# bluetooth-v12.net
KiCad netlist of a schematic drawn in EAGLE
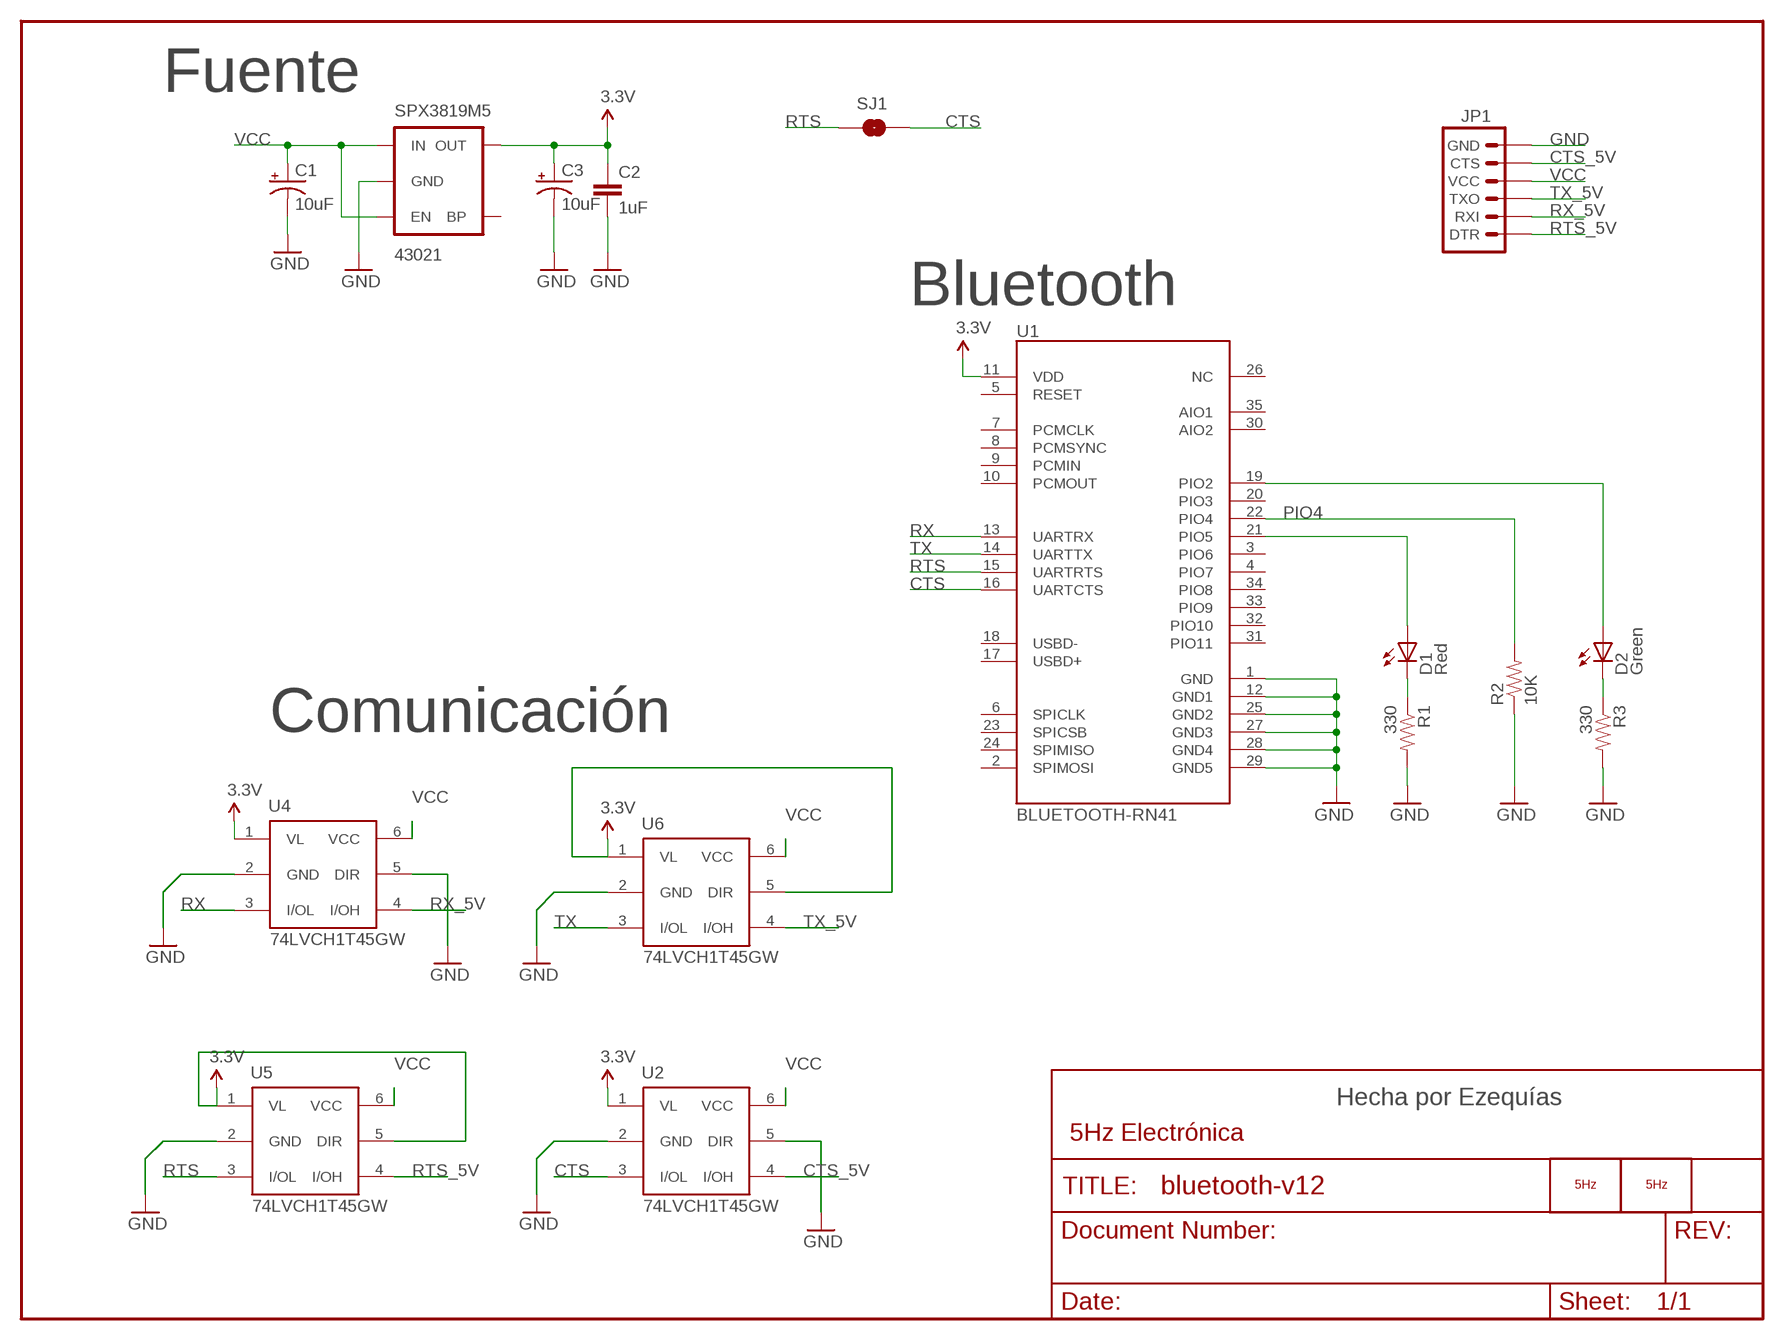
[diagram p0: schematic, sheet 1]

(export (version "E")
  (design (tool "Eeschema 10.0.6"))
  (components
    (comp (ref "C1")
      (value "10uF")
      (footprint "eagle-import:EIA3216")
      (libsource (lib "eagle-import") (part "CAP_POL1206"))
    )
    (comp (ref "C2")
      (value "1uF")
      (footprint "eagle-import:0603-CAP")
      (libsource (lib "eagle-import") (part "CAP0603-CAP"))
    )
    (comp (ref "C3")
      (value "10uF")
      (footprint "eagle-import:EIA3216")
      (libsource (lib "eagle-import") (part "CAP_POL1206"))
    )
    (comp (ref "D1")
      (value "Red")
      (footprint "eagle-import:LED-0603")
      (libsource (lib "eagle-import") (part "LED0603"))
    )
    (comp (ref "D2")
      (value "Green")
      (footprint "eagle-import:LED-0603")
      (libsource (lib "eagle-import") (part "LED0603"))
    )
    (comp (ref "JP1")
      (value "ARDUINO_SERIAL_PROGRAMPTH")
      (footprint "eagle-import:1X06")
      (libsource (lib "eagle-import") (part "ARDUINO_SERIAL_PROGRAMPTH"))
    )
    (comp (ref "LOGO2")
      (value "LOGO_5HZ_H_5MM")
      (footprint "eagle-import:5HZ_LOGO_H_5MM")
      (libsource (lib "eagle-import") (part "LOGO_5HZ_H_5MM"))
    )
    (comp (ref "LOGO3")
      (value "LOGO_5HZ_H_15MM")
      (footprint "eagle-import:5HZ_LOGO_H_15MM")
      (libsource (lib "eagle-import") (part "LOGO_5HZ_H_15MM"))
    )
    (comp (ref "R1")
      (value "330")
      (footprint "eagle-import:0603-RES")
      (libsource (lib "eagle-import") (part "RESISTOR0603-RES"))
    )
    (comp (ref "R2")
      (value "10K")
      (footprint "eagle-import:0603-RES")
      (libsource (lib "eagle-import") (part "RESISTOR0603-RES"))
    )
    (comp (ref "R3")
      (value "330")
      (footprint "eagle-import:0603-RES")
      (libsource (lib "eagle-import") (part "RESISTOR0603-RES"))
    )
    (comp (ref "SJ1")
      (value "SOLDERJUMPERNO")
      (footprint "eagle-import:SJ_2S-NO")
      (libsource (lib "eagle-import") (part "SOLDERJUMPERNO"))
    )
    (comp (ref "SPX3819M5")
      (value "43021")
      (footprint "eagle-import:SOT23-5")
      (libsource (lib "eagle-import") (part "V_REG_LDOSMD"))
    )
    (comp (ref "U1")
      (value "BLUETOOTH-RN41")
      (footprint "eagle-import:RN41")
      (libsource (lib "eagle-import") (part "BLUETOOTH-RN41{dblquote}"))
    )
    (comp (ref "U2")
      (value "74LVCH1T45GW")
      (footprint "eagle-import:SOT-363")
      (libsource (lib "eagle-import") (part "74LVCH1T45GW"))
    )
    (comp (ref "U4")
      (value "74LVCH1T45GW")
      (footprint "eagle-import:SOT-363")
      (libsource (lib "eagle-import") (part "74LVCH1T45GW"))
    )
    (comp (ref "U5")
      (value "74LVCH1T45GW")
      (footprint "eagle-import:SOT-363")
      (libsource (lib "eagle-import") (part "74LVCH1T45GW"))
    )
    (comp (ref "U6")
      (value "74LVCH1T45GW")
      (footprint "eagle-import:SOT-363")
      (libsource (lib "eagle-import") (part "74LVCH1T45GW"))
    )
  )
  (nets
    (net (code "1") (name "/CTS") (class "Default")
      (node (ref "SJ1") (pin "2") (pinfunction "2_2") (pintype "passive"))
      (node (ref "U1") (pin "16") (pinfunction "UARTCTS_16") (pintype "bidirectional"))
      (node (ref "U2") (pin "3") (pinfunction "I/OL_3") (pintype "bidirectional"))
    )
    (net (code "2") (name "/CTS_5V") (class "Default")
      (node (ref "JP1") (pin "5") (pinfunction "CTS_5") (pintype "passive"))
      (node (ref "U2") (pin "4") (pinfunction "I/OH_4") (pintype "bidirectional"))
    )
    (net (code "3") (name "/PIO4") (class "Default")
      (node (ref "R2") (pin "2") (pinfunction "2_2") (pintype "passive"))
      (node (ref "U1") (pin "22") (pinfunction "PIO4_22") (pintype "bidirectional"))
    )
    (net (code "4") (name "/RTS") (class "Default")
      (node (ref "SJ1") (pin "1") (pinfunction "1_1") (pintype "passive"))
      (node (ref "U1") (pin "15") (pinfunction "UARTRTS_15") (pintype "bidirectional"))
      (node (ref "U5") (pin "3") (pinfunction "I/OL_3") (pintype "bidirectional"))
    )
    (net (code "5") (name "/RTS_5V") (class "Default")
      (node (ref "JP1") (pin "1") (pinfunction "DTR_1") (pintype "passive"))
      (node (ref "U5") (pin "4") (pinfunction "I/OH_4") (pintype "bidirectional"))
    )
    (net (code "6") (name "/RX") (class "Default")
      (node (ref "U1") (pin "13") (pinfunction "UARTRX_13") (pintype "bidirectional"))
      (node (ref "U4") (pin "3") (pinfunction "I/OL_3") (pintype "bidirectional"))
    )
    (net (code "7") (name "/RX_5V") (class "Default")
      (node (ref "JP1") (pin "2") (pinfunction "RXI_2") (pintype "passive"))
      (node (ref "U4") (pin "4") (pinfunction "I/OH_4") (pintype "bidirectional"))
    )
    (net (code "8") (name "/TX") (class "Default")
      (node (ref "U1") (pin "14") (pinfunction "UARTTX_14") (pintype "bidirectional"))
      (node (ref "U6") (pin "3") (pinfunction "I/OL_3") (pintype "bidirectional"))
    )
    (net (code "9") (name "/TX_5V") (class "Default")
      (node (ref "JP1") (pin "3") (pinfunction "TXO_3") (pintype "passive"))
      (node (ref "U6") (pin "4") (pinfunction "I/OH_4") (pintype "bidirectional"))
    )
    (net (code "10") (name "/VCC") (class "Default")
      (node (ref "C1") (pin "A") (pinfunction "+_A") (pintype "passive"))
      (node (ref "JP1") (pin "4") (pinfunction "VCC_4") (pintype "passive"))
      (node (ref "SPX3819M5") (pin "1") (pinfunction "IN_1") (pintype "input"))
      (node (ref "SPX3819M5") (pin "3") (pinfunction "EN_3") (pintype "input"))
      (node (ref "U2") (pin "6") (pinfunction "VCC_6") (pintype "bidirectional"))
      (node (ref "U4") (pin "6") (pinfunction "VCC_6") (pintype "bidirectional"))
      (node (ref "U5") (pin "6") (pinfunction "VCC_6") (pintype "bidirectional"))
      (node (ref "U6") (pin "6") (pinfunction "VCC_6") (pintype "bidirectional"))
    )
    (net (code "11") (name "3.3V") (class "Default")
      (node (ref "C2") (pin "1") (pinfunction "1_1") (pintype "passive"))
      (node (ref "C3") (pin "A") (pinfunction "+_A") (pintype "passive"))
      (node (ref "SPX3819M5") (pin "5") (pinfunction "OUT_5") (pintype "passive"))
      (node (ref "U1") (pin "11") (pinfunction "VDD_11") (pintype "bidirectional"))
      (node (ref "U2") (pin "1") (pinfunction "VL_1") (pintype "bidirectional"))
      (node (ref "U4") (pin "1") (pinfunction "VL_1") (pintype "bidirectional"))
      (node (ref "U5") (pin "1") (pinfunction "VL_1") (pintype "bidirectional"))
      (node (ref "U5") (pin "5") (pinfunction "DIR_5") (pintype "bidirectional"))
      (node (ref "U6") (pin "1") (pinfunction "VL_1") (pintype "bidirectional"))
      (node (ref "U6") (pin "5") (pinfunction "DIR_5") (pintype "bidirectional"))
    )
    (net (code "12") (name "GND") (class "Default")
      (node (ref "C1") (pin "C") (pinfunction "-_C") (pintype "passive"))
      (node (ref "C2") (pin "2") (pinfunction "2_2") (pintype "passive"))
      (node (ref "C3") (pin "C") (pinfunction "-_C") (pintype "passive"))
      (node (ref "JP1") (pin "6") (pinfunction "GND_6") (pintype "passive"))
      (node (ref "R1") (pin "2") (pinfunction "2_2") (pintype "passive"))
      (node (ref "R2") (pin "1") (pinfunction "1_1") (pintype "passive"))
      (node (ref "R3") (pin "2") (pinfunction "2_2") (pintype "passive"))
      (node (ref "SPX3819M5") (pin "2") (pinfunction "GND_2") (pintype "input"))
      (node (ref "U1") (pin "1") (pinfunction "GND_1") (pintype "bidirectional"))
      (node (ref "U1") (pin "12") (pinfunction "GND1_12") (pintype "bidirectional"))
      (node (ref "U1") (pin "25") (pinfunction "GND2_25") (pintype "bidirectional"))
      (node (ref "U1") (pin "27") (pinfunction "GND3_27") (pintype "bidirectional"))
      (node (ref "U1") (pin "28") (pinfunction "GND4_28") (pintype "bidirectional"))
      (node (ref "U1") (pin "29") (pinfunction "GND5_29") (pintype "bidirectional"))
      (node (ref "U2") (pin "2") (pinfunction "GND_2") (pintype "bidirectional"))
      (node (ref "U2") (pin "5") (pinfunction "DIR_5") (pintype "bidirectional"))
      (node (ref "U4") (pin "2") (pinfunction "GND_2") (pintype "bidirectional"))
      (node (ref "U4") (pin "5") (pinfunction "DIR_5") (pintype "bidirectional"))
      (node (ref "U5") (pin "2") (pinfunction "GND_2") (pintype "bidirectional"))
      (node (ref "U6") (pin "2") (pinfunction "GND_2") (pintype "bidirectional"))
    )
    (net (code "13") (name "Net-(D1-PadC)") (class "Default")
      (node (ref "D1") (pin "C") (pinfunction "C_C") (pintype "passive"))
      (node (ref "R1") (pin "1") (pinfunction "1_1") (pintype "passive"))
    )
    (net (code "14") (name "Net-(D2-PadC)") (class "Default")
      (node (ref "D2") (pin "C") (pinfunction "C_C") (pintype "passive"))
      (node (ref "R3") (pin "1") (pinfunction "1_1") (pintype "passive"))
    )
    (net (code "15") (name "Net-(U1-PIO2)") (class "Default")
      (node (ref "D2") (pin "A") (pinfunction "A_A") (pintype "passive"))
      (node (ref "U1") (pin "19") (pinfunction "PIO2_19") (pintype "bidirectional"))
    )
    (net (code "16") (name "Net-(U1-PIO5)") (class "Default")
      (node (ref "D1") (pin "A") (pinfunction "A_A") (pintype "passive"))
      (node (ref "U1") (pin "21") (pinfunction "PIO5_21") (pintype "bidirectional"))
    )
    (net (code "17") (name "unconnected-(SPX3819M5-BP-Pad4)") (class "Default")
      (node (ref "SPX3819M5") (pin "4") (pinfunction "BP_4") (pintype "input"))
    )
    (net (code "18") (name "unconnected-(U1-AIO1-Pad35)") (class "Default")
      (node (ref "U1") (pin "35") (pinfunction "AIO1_35") (pintype "bidirectional"))
    )
    (net (code "19") (name "unconnected-(U1-AIO2-Pad30)") (class "Default")
      (node (ref "U1") (pin "30") (pinfunction "AIO2_30") (pintype "bidirectional"))
    )
    (net (code "20") (name "unconnected-(U1-NC-Pad26)") (class "Default")
      (node (ref "U1") (pin "26") (pinfunction "NC_26") (pintype "bidirectional"))
    )
    (net (code "21") (name "unconnected-(U1-PCMCLK-Pad7)") (class "Default")
      (node (ref "U1") (pin "7") (pinfunction "PCMCLK_7") (pintype "bidirectional"))
    )
    (net (code "22") (name "unconnected-(U1-PCMIN-Pad9)") (class "Default")
      (node (ref "U1") (pin "9") (pinfunction "PCMIN_9") (pintype "bidirectional"))
    )
    (net (code "23") (name "unconnected-(U1-PCMOUT-Pad10)") (class "Default")
      (node (ref "U1") (pin "10") (pinfunction "PCMOUT_10") (pintype "bidirectional"))
    )
    (net (code "24") (name "unconnected-(U1-PCMSYNC-Pad8)") (class "Default")
      (node (ref "U1") (pin "8") (pinfunction "PCMSYNC_8") (pintype "bidirectional"))
    )
    (net (code "25") (name "unconnected-(U1-PIO3-Pad20)") (class "Default")
      (node (ref "U1") (pin "20") (pinfunction "PIO3_20") (pintype "bidirectional"))
    )
    (net (code "26") (name "unconnected-(U1-PIO6-Pad3)") (class "Default")
      (node (ref "U1") (pin "3") (pinfunction "PIO6_3") (pintype "bidirectional"))
    )
    (net (code "27") (name "unconnected-(U1-PIO7-Pad4)") (class "Default")
      (node (ref "U1") (pin "4") (pinfunction "PIO7_4") (pintype "bidirectional"))
    )
    (net (code "28") (name "unconnected-(U1-PIO8-Pad34)") (class "Default")
      (node (ref "U1") (pin "34") (pinfunction "PIO8_34") (pintype "bidirectional"))
    )
    (net (code "29") (name "unconnected-(U1-PIO9-Pad33)") (class "Default")
      (node (ref "U1") (pin "33") (pinfunction "PIO9_33") (pintype "bidirectional"))
    )
    (net (code "30") (name "unconnected-(U1-PIO10-Pad32)") (class "Default")
      (node (ref "U1") (pin "32") (pinfunction "PIO10_32") (pintype "bidirectional"))
    )
    (net (code "31") (name "unconnected-(U1-PIO11-Pad31)") (class "Default")
      (node (ref "U1") (pin "31") (pinfunction "PIO11_31") (pintype "bidirectional"))
    )
    (net (code "32") (name "unconnected-(U1-RESET-Pad5)") (class "Default")
      (node (ref "U1") (pin "5") (pinfunction "RESET_5") (pintype "bidirectional"))
    )
    (net (code "33") (name "unconnected-(U1-SPICLK-Pad6)") (class "Default")
      (node (ref "U1") (pin "6") (pinfunction "SPICLK_6") (pintype "bidirectional"))
    )
    (net (code "34") (name "unconnected-(U1-SPICSB-Pad23)") (class "Default")
      (node (ref "U1") (pin "23") (pinfunction "SPICSB_23") (pintype "bidirectional"))
    )
    (net (code "35") (name "unconnected-(U1-SPIMISO-Pad24)") (class "Default")
      (node (ref "U1") (pin "24") (pinfunction "SPIMISO_24") (pintype "bidirectional"))
    )
    (net (code "36") (name "unconnected-(U1-SPIMOSI-Pad2)") (class "Default")
      (node (ref "U1") (pin "2") (pinfunction "SPIMOSI_2") (pintype "bidirectional"))
    )
    (net (code "37") (name "unconnected-(U1-USBD+-Pad17)") (class "Default")
      (node (ref "U1") (pin "17") (pinfunction "USBD+_17") (pintype "bidirectional"))
    )
    (net (code "38") (name "unconnected-(U1-USBD--Pad18)") (class "Default")
      (node (ref "U1") (pin "18") (pinfunction "USBD-_18") (pintype "bidirectional"))
    )
  )
)
